# CKT_C70005-A2.net
KiCad netlist of a schematic drawn in Altium Designer
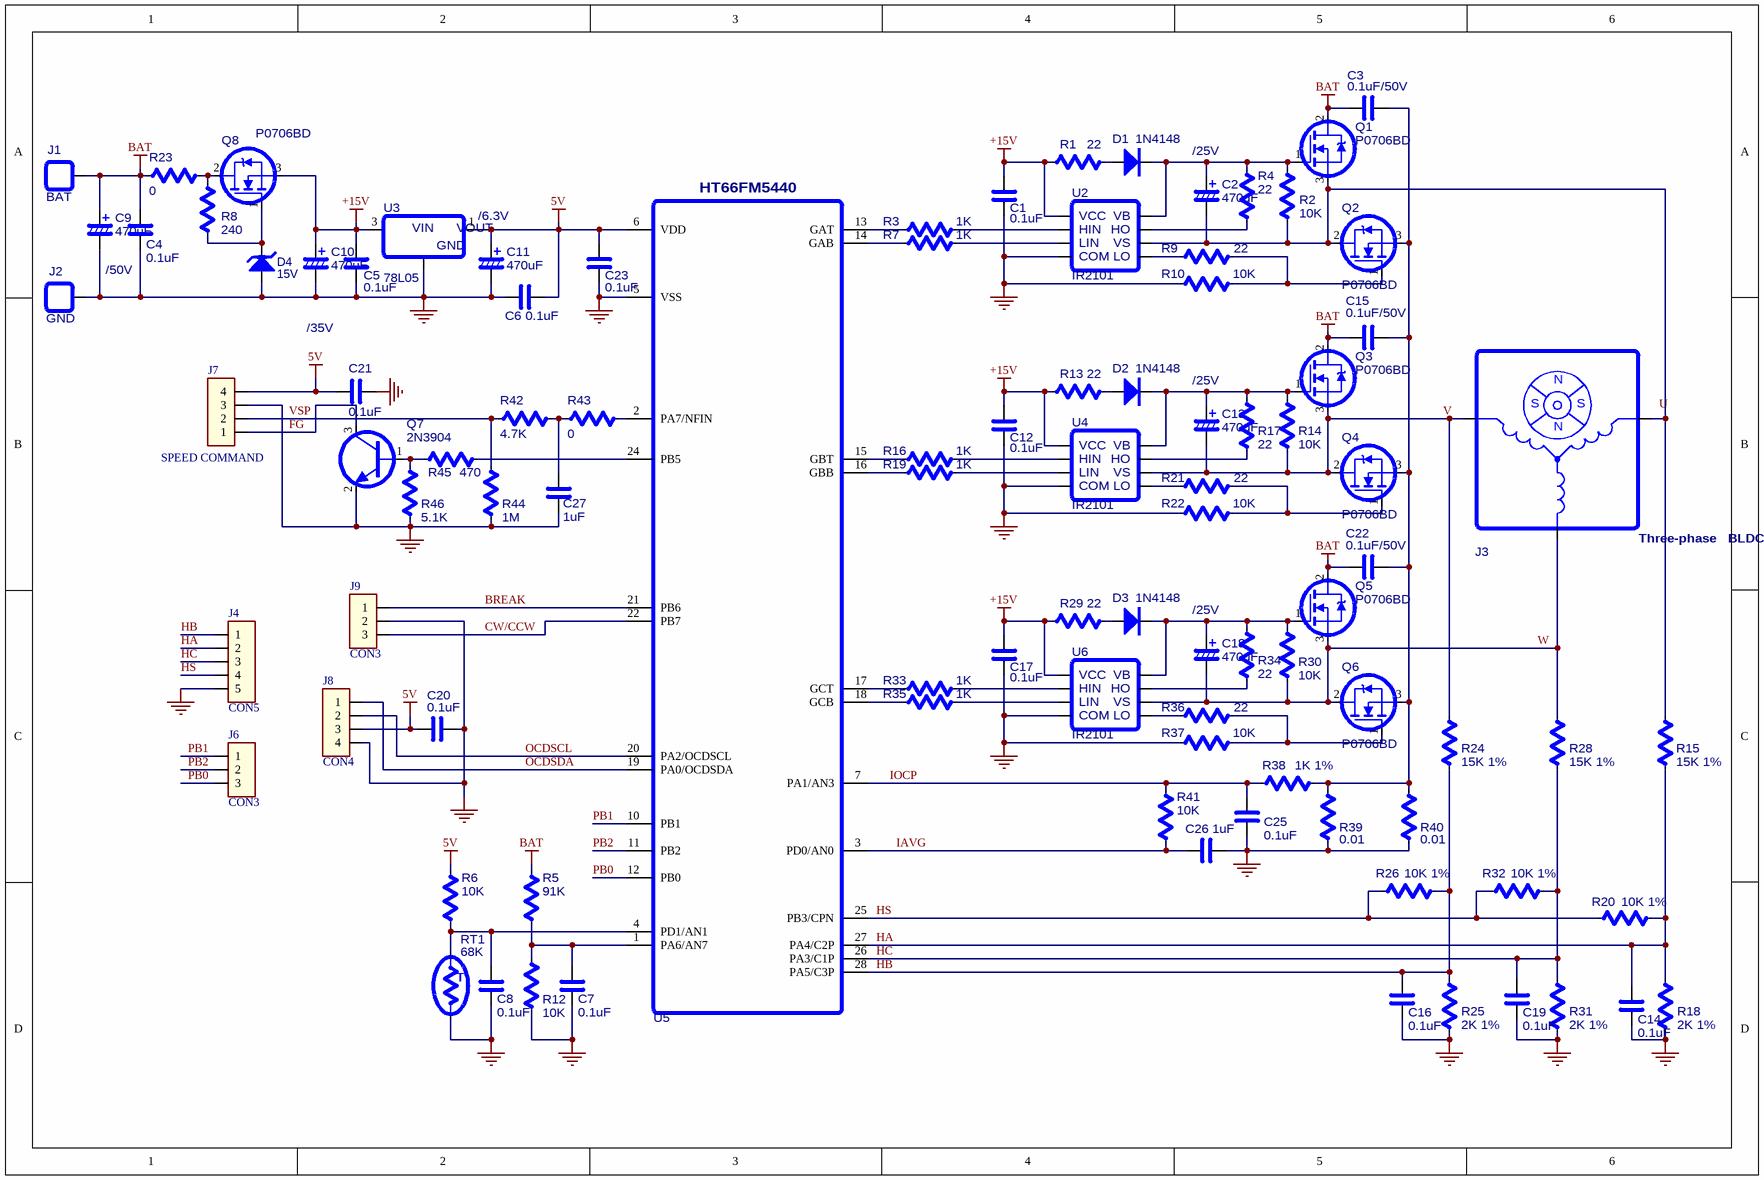
[diagram p0: CKT_C70005-A2.SchDoc]

(export (version "E")
  (design (tool "Eeschema 10.0.6"))
  (components
    (comp (ref "C1")
      (value "0.1uF")
      (description "Capacitor")
      (fields (field (name "PUBLISHER") "Altium Limited"))
      (libsource (lib "Holtek Component Library V2") (part "Cap(1)"))
    )
    (comp (ref "C2")
      (value "470uF")
      (footprint "0805C")
      (description "Capacitor")
      (libsource (lib "C70005") (part "Cap(2)"))
    )
    (comp (ref "C3")
      (value "0.1uF/50V")
      (description "Capacitor")
      (fields (field (name "PUBLISHER") "Altium Limited"))
      (libsource (lib "Holtek Component Library V2") (part "Cap(1)"))
    )
    (comp (ref "C4")
      (value "0.1uF")
      (description "Capacitor")
      (fields (field (name "PUBLISHER") "Altium Limited"))
      (libsource (lib "Holtek Component Library V2") (part "Cap(1)"))
    )
    (comp (ref "C5")
      (value "0.1uF")
      (description "Capacitor")
      (fields (field (name "PUBLISHER") "Altium Limited"))
      (libsource (lib "Holtek Component Library V2") (part "Cap(1)"))
    )
    (comp (ref "C6")
      (value "0.1uF")
      (description "Capacitor")
      (fields (field (name "PUBLISHER") "Altium Limited"))
      (libsource (lib "Holtek Component Library V2") (part "Cap(1)"))
    )
    (comp (ref "C7")
      (value "0.1uF")
      (description "Capacitor")
      (fields (field (name "PUBLISHER") "Altium Limited"))
      (libsource (lib "Holtek Component Library V2") (part "Cap(1)"))
    )
    (comp (ref "C8")
      (value "0.1uF")
      (description "Capacitor")
      (fields (field (name "PUBLISHER") "Altium Limited"))
      (libsource (lib "Holtek Component Library V2") (part "Cap(1)"))
    )
    (comp (ref "C9")
      (value "470uF")
      (footprint "CD-10.5*21")
      (description "Capacitor")
      (libsource (lib "C70005") (part "Cap(2)"))
    )
    (comp (ref "C10")
      (value "470uF")
      (footprint "ECAP 35V47UF")
      (description "Capacitor")
      (libsource (lib "C70005") (part "Cap(2)"))
    )
    (comp (ref "C11")
      (value "470uF")
      (footprint "ECAP 35V47UF")
      (description "Capacitor")
      (libsource (lib "C70005") (part "Cap(2)"))
    )
    (comp (ref "C12")
      (value "0.1uF")
      (description "Capacitor")
      (fields (field (name "PUBLISHER") "Altium Limited"))
      (libsource (lib "Holtek Component Library V2") (part "Cap(1)"))
    )
    (comp (ref "C13")
      (value "470uF")
      (footprint "0805C")
      (description "Capacitor")
      (libsource (lib "C70005") (part "Cap(2)"))
    )
    (comp (ref "C14")
      (value "0.1uF")
      (footprint "0603C")
      (description "Capacitor")
      (fields (field (name "PUBLISHER") "Altium Limited"))
      (libsource (lib "Holtek Component Library V2") (part "Cap(1)"))
    )
    (comp (ref "C15")
      (value "0.1uF/50V")
      (description "Capacitor")
      (fields (field (name "PUBLISHER") "Altium Limited"))
      (libsource (lib "Holtek Component Library V2") (part "Cap(1)"))
    )
    (comp (ref "C16")
      (value "0.1uF")
      (footprint "0603C")
      (description "Capacitor")
      (fields (field (name "PUBLISHER") "Altium Limited"))
      (libsource (lib "Holtek Component Library V2") (part "Cap(1)"))
    )
    (comp (ref "C17")
      (value "0.1uF")
      (description "Capacitor")
      (fields (field (name "PUBLISHER") "Altium Limited"))
      (libsource (lib "Holtek Component Library V2") (part "Cap(1)"))
    )
    (comp (ref "C18")
      (value "470uF")
      (footprint "0805C")
      (description "Capacitor")
      (libsource (lib "C70005") (part "Cap(2)"))
    )
    (comp (ref "C19")
      (value "0.1uF")
      (footprint "0603C")
      (description "Capacitor")
      (fields (field (name "PUBLISHER") "Altium Limited"))
      (libsource (lib "Holtek Component Library V2") (part "Cap(1)"))
    )
    (comp (ref "C20")
      (value "0.1uF")
      (footprint "0603c")
      (description "Capacitor")
      (fields (field (name "PUBLISHER") "Altium Limited"))
      (libsource (lib "Holtek Component Library V2") (part "Cap(1)"))
    )
    (comp (ref "C21")
      (value "0.1uF")
      (footprint "0603c")
      (description "Capacitor")
      (fields (field (name "PUBLISHER") "Altium Limited"))
      (libsource (lib "Holtek Component Library V2") (part "Cap(1)"))
    )
    (comp (ref "C22")
      (value "0.1uF/50V")
      (description "Capacitor")
      (fields (field (name "PUBLISHER") "Altium Limited"))
      (libsource (lib "Holtek Component Library V2") (part "Cap(1)"))
    )
    (comp (ref "C23")
      (value "0.1uF")
      (description "Capacitor")
      (fields (field (name "PUBLISHER") "Altium Limited"))
      (libsource (lib "Holtek Component Library V2") (part "Cap(1)"))
    )
    (comp (ref "C25")
      (value "0.1uF")
      (description "Capacitor")
      (fields (field (name "PUBLISHER") "Altium Limited"))
      (libsource (lib "Holtek Component Library V2") (part "Cap(1)"))
    )
    (comp (ref "C26")
      (value "1uF")
      (description "Capacitor")
      (fields (field (name "PUBLISHER") "Altium Limited"))
      (libsource (lib "Holtek Component Library V2") (part "Cap(1)"))
    )
    (comp (ref "C27")
      (value "1uF")
      (description "Capacitor")
      (fields (field (name "PUBLISHER") "Altium Limited"))
      (libsource (lib "Holtek Component Library V2") (part "Cap(1)"))
    )
    (comp (ref "D1")
      (value "1N4148")
      (footprint "1206D")
      (description "Diode")
      (fields (field (name "PUBLISHER") "Altium Limited"))
      (libsource (lib "Holtek Component Library V2") (part "Diode(1)"))
    )
    (comp (ref "D2")
      (value "1N4148")
      (footprint "1206D")
      (description "Diode")
      (fields (field (name "PUBLISHER") "Altium Limited"))
      (libsource (lib "Holtek Component Library V2") (part "Diode(1)"))
    )
    (comp (ref "D3")
      (value "1N4148")
      (footprint "1206D")
      (description "Diode")
      (fields (field (name "PUBLISHER") "Altium Limited"))
      (libsource (lib "Holtek Component Library V2") (part "Diode(1)"))
    )
    (comp (ref "D4")
      (value "15V")
      (footprint "1206D")
      (description "Zener Diode")
      (libsource (lib "Holtek Component Library V2(Chris)") (part "Zener(1)"))
    )
    (comp (ref "J1")
      (value "BAT")
      (footprint "SIP1-big")
      (description "CON1")
      (fields (field (name "PUBLISHER") "Altium Limited"))
      (libsource (lib "C70005-A1") (part "CON1"))
    )
    (comp (ref "J2")
      (value "GND")
      (footprint "SIP1-big")
      (description "CON1")
      (fields (field (name "PUBLISHER") "Altium Limited"))
      (libsource (lib "C70005-A1") (part "CON1"))
    )
    (comp (ref "J3") (value "BLDC motor(1)") (libsource (lib "C70005") (part "BLDC motor(1)_1")))
    (comp (ref "J4") (value "CON5") (libsource (lib "MYLIB") (part "CON5")))
    (comp (ref "J6") (value "CON3") (libsource (lib "MYLIB") (part "CON3")))
    (comp (ref "J7") (value "SPEED COMMAND") (footprint "HDR1X4") (libsource (lib "") (part "CON4_1")))
    (comp (ref "J8") (value "CON4") (footprint "SIP4") (libsource (lib "MYLIB") (part "CON4")))
    (comp (ref "J9") (value "CON3") (footprint "SIP3-2.54mm") (libsource (lib "") (part "CON3_1")))
    (comp (ref "Q1")
      (value "P0706BD")
      (footprint "TO252")
      (description "N-Channel Power MOSFET")
      (fields (field (name "PUBLISHER") "Altium Limited"))
      (libsource (lib "C70005") (part "NMOS(4)"))
    )
    (comp (ref "Q2")
      (value "P0706BD")
      (footprint "TO252")
      (description "N-Channel Power MOSFET")
      (fields (field (name "PUBLISHER") "Altium Limited"))
      (libsource (lib "C70005") (part "NMOS(4)"))
    )
    (comp (ref "Q3")
      (value "P0706BD")
      (footprint "TO252")
      (description "N-Channel Power MOSFET")
      (fields (field (name "PUBLISHER") "Altium Limited"))
      (libsource (lib "C70005") (part "NMOS(4)"))
    )
    (comp (ref "Q4")
      (value "P0706BD")
      (footprint "TO252")
      (description "N-Channel Power MOSFET")
      (fields (field (name "PUBLISHER") "Altium Limited"))
      (libsource (lib "C70005") (part "NMOS(4)"))
    )
    (comp (ref "Q5")
      (value "P0706BD")
      (footprint "TO252")
      (description "N-Channel Power MOSFET")
      (fields (field (name "PUBLISHER") "Altium Limited"))
      (libsource (lib "C70005") (part "NMOS(4)"))
    )
    (comp (ref "Q6")
      (value "P0706BD")
      (footprint "TO252")
      (description "N-Channel Power MOSFET")
      (fields (field (name "PUBLISHER") "Altium Limited"))
      (libsource (lib "C70005") (part "NMOS(4)"))
    )
    (comp (ref "Q7")
      (value "2N3904")
      (footprint "SOT-23")
      (description "NPN Bipolar Transistor")
      (fields (field (name "PUBLISHER") "Altium Limited"))
      (libsource (lib "C70005") (part "NPN(2)"))
    )
    (comp (ref "Q8")
      (value "P0706BD")
      (footprint "TO252")
      (description "N-Channel Power MOSFET")
      (fields (field (name "PUBLISHER") "Altium Limited"))
      (libsource (lib "C70005") (part "NMOS(4)"))
    )
    (comp (ref "R1")
      (value "22")
      (description "Resisitor")
      (libsource (lib "Holtek Component Library V2") (part "Resistor(1)_1"))
    )
    (comp (ref "R2")
      (value "10K")
      (description "Resisitor")
      (libsource (lib "Holtek Component Library V2") (part "Resistor(1)_1"))
    )
    (comp (ref "R3")
      (value "1K")
      (description "Resisitor")
      (libsource (lib "Holtek Component Library V2") (part "Resistor(1)_1"))
    )
    (comp (ref "R4")
      (value "22")
      (description "Resisitor")
      (libsource (lib "Holtek Component Library V2") (part "Resistor(1)_1"))
    )
    (comp (ref "R5")
      (value "91K")
      (description "Resisitor")
      (libsource (lib "Holtek Component Library V2") (part "Resistor(1)_1"))
    )
    (comp (ref "R6")
      (value "10K")
      (description "Resisitor")
      (libsource (lib "Holtek Component Library V2") (part "Resistor(1)_1"))
    )
    (comp (ref "R7")
      (value "1K")
      (description "Resisitor")
      (libsource (lib "Holtek Component Library V2") (part "Resistor(1)_1"))
    )
    (comp (ref "R8")
      (value "240")
      (description "Resisitor")
      (libsource (lib "Holtek Component Library V2") (part "Resistor(1)_1"))
    )
    (comp (ref "R9")
      (value "22")
      (description "Resisitor")
      (libsource (lib "Holtek Component Library V2") (part "Resistor(1)_1"))
    )
    (comp (ref "R10")
      (value "10K")
      (description "Resisitor")
      (libsource (lib "Holtek Component Library V2") (part "Resistor(1)_1"))
    )
    (comp (ref "R12")
      (value "10K")
      (description "Resisitor")
      (libsource (lib "Holtek Component Library V2") (part "Resistor(1)_1"))
    )
    (comp (ref "R13")
      (value "22")
      (description "Resisitor")
      (libsource (lib "Holtek Component Library V2") (part "Resistor(1)_1"))
    )
    (comp (ref "R14")
      (value "10K")
      (description "Resisitor")
      (libsource (lib "Holtek Component Library V2") (part "Resistor(1)_1"))
    )
    (comp (ref "R15")
      (value "15K 1%")
      (description "Resisitor")
      (libsource (lib "Holtek Component Library V2") (part "Resistor(1)_1"))
    )
    (comp (ref "R16")
      (value "1K")
      (description "Resisitor")
      (libsource (lib "Holtek Component Library V2") (part "Resistor(1)_1"))
    )
    (comp (ref "R17")
      (value "22")
      (description "Resisitor")
      (libsource (lib "Holtek Component Library V2") (part "Resistor(1)_1"))
    )
    (comp (ref "R18")
      (value "2K 1%")
      (description "Resisitor")
      (libsource (lib "Holtek Component Library V2") (part "Resistor(1)_1"))
    )
    (comp (ref "R19")
      (value "1K")
      (description "Resisitor")
      (libsource (lib "Holtek Component Library V2") (part "Resistor(1)_1"))
    )
    (comp (ref "R20")
      (value "10K 1%")
      (description "Resisitor")
      (libsource (lib "Holtek Component Library V2") (part "Resistor(1)_1"))
    )
    (comp (ref "R21")
      (value "22")
      (description "Resisitor")
      (libsource (lib "Holtek Component Library V2") (part "Resistor(1)_1"))
    )
    (comp (ref "R22")
      (value "10K")
      (description "Resisitor")
      (libsource (lib "Holtek Component Library V2") (part "Resistor(1)_1"))
    )
    (comp (ref "R23")
      (value "0")
      (description "Resisitor")
      (libsource (lib "Holtek Component Library V2") (part "Resistor(1)_1"))
    )
    (comp (ref "R24")
      (value "15K 1%")
      (description "Resisitor")
      (libsource (lib "Holtek Component Library V2") (part "Resistor(1)_1"))
    )
    (comp (ref "R25")
      (value "2K 1%")
      (description "Resisitor")
      (libsource (lib "Holtek Component Library V2") (part "Resistor(1)_1"))
    )
    (comp (ref "R26")
      (value "10K 1%")
      (description "Resisitor")
      (libsource (lib "Holtek Component Library V2") (part "Resistor(1)_1"))
    )
    (comp (ref "R28")
      (value "15K 1%")
      (description "Resisitor")
      (libsource (lib "Holtek Component Library V2") (part "Resistor(1)_1"))
    )
    (comp (ref "R29")
      (value "22")
      (description "Resisitor")
      (libsource (lib "Holtek Component Library V2") (part "Resistor(1)_1"))
    )
    (comp (ref "R30")
      (value "10K")
      (description "Resisitor")
      (libsource (lib "Holtek Component Library V2") (part "Resistor(1)_1"))
    )
    (comp (ref "R31")
      (value "2K 1%")
      (description "Resisitor")
      (libsource (lib "Holtek Component Library V2") (part "Resistor(1)_1"))
    )
    (comp (ref "R32")
      (value "10K 1%")
      (description "Resisitor")
      (libsource (lib "Holtek Component Library V2") (part "Resistor(1)_1"))
    )
    (comp (ref "R33")
      (value "1K")
      (description "Resisitor")
      (libsource (lib "Holtek Component Library V2") (part "Resistor(1)_1"))
    )
    (comp (ref "R34")
      (value "22")
      (description "Resisitor")
      (libsource (lib "Holtek Component Library V2") (part "Resistor(1)_1"))
    )
    (comp (ref "R35")
      (value "1K")
      (description "Resisitor")
      (libsource (lib "Holtek Component Library V2") (part "Resistor(1)_1"))
    )
    (comp (ref "R36")
      (value "22")
      (description "Resisitor")
      (libsource (lib "Holtek Component Library V2") (part "Resistor(1)_1"))
    )
    (comp (ref "R37")
      (value "10K")
      (description "Resisitor")
      (libsource (lib "Holtek Component Library V2") (part "Resistor(1)_1"))
    )
    (comp (ref "R38")
      (value "1K 1%")
      (description "Resisitor")
      (libsource (lib "Holtek Component Library V2") (part "Resistor(1)_1"))
    )
    (comp (ref "R39")
      (value "0.01")
      (description "Resisitor")
      (libsource (lib "Holtek Component Library V2") (part "Resistor(1)_1"))
    )
    (comp (ref "R40")
      (value "0.01")
      (description "Resisitor")
      (libsource (lib "Holtek Component Library V2") (part "Resistor(1)_1"))
    )
    (comp (ref "R41")
      (value "10K")
      (description "Resisitor")
      (libsource (lib "Holtek Component Library V2") (part "Resistor(1)_1"))
    )
    (comp (ref "R42")
      (value "4.7K")
      (description "Resisitor")
      (libsource (lib "Holtek Component Library V2") (part "Resistor(1)_1"))
    )
    (comp (ref "R43")
      (value "0")
      (description "Resisitor")
      (libsource (lib "Holtek Component Library V2") (part "Resistor(1)_1"))
    )
    (comp (ref "R44")
      (value "1M")
      (description "Resisitor")
      (libsource (lib "Holtek Component Library V2") (part "Resistor(1)_1"))
    )
    (comp (ref "R45")
      (value "470")
      (description "Resisitor")
      (libsource (lib "Holtek Component Library V2") (part "Resistor(1)_1"))
    )
    (comp (ref "R46")
      (value "5.1K")
      (description "Resisitor")
      (libsource (lib "Holtek Component Library V2") (part "Resistor(1)_1"))
    )
    (comp (ref "RT1") (value "68K") (libsource (lib "Holtek Component Library V2") (part "Sensor(1)")))
    (comp (ref "U2") (value "IR2101") (footprint "SOP-8") (libsource (lib "C70005") (part "IR2101/SOP-8")))
    (comp (ref "U3") (value "78L05") (footprint "SOT-89") (libsource (lib "C70005") (part "78L05_1")))
    (comp (ref "U4") (value "IR2101") (footprint "SOP-8") (libsource (lib "C70005") (part "IR2101/SOP-8")))
    (comp (ref "U5")
      (value "HT66FM5440/28SSOP")
      (footprint "SSOP28")
      (libsource (lib "C70005") (part "HT66FM5440/28SSOP"))
    )
    (comp (ref "U6") (value "IR2101") (footprint "SOP-8") (libsource (lib "C70005") (part "IR2101/SOP-8")))
  )
  (nets
    (net (code "1") (name "+15V") (class "Default")
      (node (ref "C1") (pin "2") (pinfunction "2_2") (pintype "passive"))
      (node (ref "C10") (pin "1") (pinfunction "1_1") (pintype "passive"))
      (node (ref "C12") (pin "2") (pinfunction "2_2") (pintype "passive"))
      (node (ref "C17") (pin "2") (pinfunction "2_2") (pintype "passive"))
      (node (ref "C5") (pin "2") (pinfunction "2_2") (pintype "passive"))
      (node (ref "Q8") (pin "3") (pinfunction "60_3") (pintype "passive"))
      (node (ref "R1") (pin "1") (pinfunction "1_1") (pintype "passive"))
      (node (ref "R13") (pin "1") (pinfunction "1_1") (pintype "passive"))
      (node (ref "R29") (pin "1") (pinfunction "1_1") (pintype "passive"))
      (node (ref "U2") (pin "1") (pinfunction "VCC_1") (pintype "passive"))
      (node (ref "U3") (pin "3") (pinfunction "Vin_3") (pintype "passive"))
      (node (ref "U4") (pin "1") (pinfunction "VCC_1") (pintype "passive"))
      (node (ref "U6") (pin "1") (pinfunction "VCC_1") (pintype "passive"))
    )
    (net (code "2") (name "/BREAK") (class "Default")
      (node (ref "J9") (pin "1") (pinfunction "1_1") (pintype "passive"))
      (node (ref "U5") (pin "21") (pinfunction "PB6_21") (pintype "passive"))
    )
    (net (code "3") (name "/CW{slash}CCW") (class "Default")
      (node (ref "J9") (pin "3") (pinfunction "3_3") (pintype "passive"))
      (node (ref "U5") (pin "22") (pinfunction "PB7_22") (pintype "passive"))
    )
    (net (code "4") (name "/FG") (class "Default")
      (node (ref "J7") (pin "1") (pinfunction "1_1") (pintype "passive"))
      (node (ref "Q7") (pin "3") (pinfunction "C_3") (pintype "passive"))
    )
    (net (code "5") (name "/HA") (class "Default")
      (node (ref "C14") (pin "2") (pinfunction "2_2") (pintype "passive"))
      (node (ref "J4") (pin "2") (pinfunction "2_2") (pintype "passive"))
      (node (ref "R15") (pin "2") (pinfunction "2_2") (pintype "passive"))
      (node (ref "R18") (pin "1") (pinfunction "1_1") (pintype "passive"))
      (node (ref "R20") (pin "2") (pinfunction "2_2") (pintype "passive"))
      (node (ref "U5") (pin "27") (pinfunction "PA4/C2P_27") (pintype "passive"))
    )
    (net (code "6") (name "/HB") (class "Default")
      (node (ref "C16") (pin "2") (pinfunction "2_2") (pintype "passive"))
      (node (ref "J4") (pin "1") (pinfunction "1_1") (pintype "passive"))
      (node (ref "R24") (pin "2") (pinfunction "2_2") (pintype "passive"))
      (node (ref "R25") (pin "1") (pinfunction "1_1") (pintype "passive"))
      (node (ref "R26") (pin "2") (pinfunction "2_2") (pintype "passive"))
      (node (ref "U5") (pin "28") (pinfunction "PA5/C3P_28") (pintype "passive"))
    )
    (net (code "7") (name "/HC") (class "Default")
      (node (ref "C19") (pin "2") (pinfunction "2_2") (pintype "passive"))
      (node (ref "J4") (pin "3") (pinfunction "3_3") (pintype "passive"))
      (node (ref "R28") (pin "2") (pinfunction "2_2") (pintype "passive"))
      (node (ref "R31") (pin "1") (pinfunction "1_1") (pintype "passive"))
      (node (ref "R32") (pin "2") (pinfunction "2_2") (pintype "passive"))
      (node (ref "U5") (pin "26") (pinfunction "PA3/C1P_26") (pintype "passive"))
    )
    (net (code "8") (name "/HS") (class "Default")
      (node (ref "J4") (pin "4") (pinfunction "4_4") (pintype "passive"))
      (node (ref "R20") (pin "1") (pinfunction "1_1") (pintype "passive"))
      (node (ref "R26") (pin "1") (pinfunction "1_1") (pintype "passive"))
      (node (ref "R32") (pin "1") (pinfunction "1_1") (pintype "passive"))
      (node (ref "U5") (pin "25") (pinfunction "PB3/CPN_25") (pintype "passive"))
    )
    (net (code "9") (name "/IAVG") (class "Default")
      (node (ref "C26") (pin "2") (pinfunction "2_2") (pintype "passive"))
      (node (ref "R41") (pin "1") (pinfunction "1_1") (pintype "passive"))
      (node (ref "U5") (pin "3") (pinfunction "PD0/AN0_3") (pintype "passive"))
    )
    (net (code "10") (name "/IOCP") (class "Default")
      (node (ref "C25") (pin "1") (pinfunction "1_1") (pintype "passive"))
      (node (ref "R38") (pin "2") (pinfunction "2_2") (pintype "passive"))
      (node (ref "R41") (pin "2") (pinfunction "2_2") (pintype "passive"))
      (node (ref "U5") (pin "7") (pinfunction "PA1/AN3_7") (pintype "passive"))
    )
    (net (code "11") (name "/OCDSCL") (class "Default")
      (node (ref "J8") (pin "2") (pinfunction "2_2") (pintype "passive"))
      (node (ref "U5") (pin "20") (pinfunction "PA2/OCDSCL_20") (pintype "passive"))
    )
    (net (code "12") (name "/OCDSDA") (class "Default")
      (node (ref "J8") (pin "1") (pinfunction "1_1") (pintype "passive"))
      (node (ref "U5") (pin "19") (pinfunction "PA0/OCDSDA_19") (pintype "passive"))
    )
    (net (code "13") (name "/PB0") (class "Default")
      (node (ref "J6") (pin "3") (pinfunction "3_3") (pintype "passive"))
      (node (ref "U5") (pin "12") (pinfunction "PB0_12") (pintype "passive"))
    )
    (net (code "14") (name "/PB1") (class "Default")
      (node (ref "J6") (pin "1") (pinfunction "1_1") (pintype "passive"))
      (node (ref "U5") (pin "10") (pinfunction "PB1_10") (pintype "passive"))
    )
    (net (code "15") (name "/PB2") (class "Default")
      (node (ref "J6") (pin "2") (pinfunction "2_2") (pintype "passive"))
      (node (ref "U5") (pin "11") (pinfunction "PB2_11") (pintype "passive"))
    )
    (net (code "17") (name "/V") (class "Default")
      (node (ref "C13") (pin "2") (pinfunction "2_2") (pintype "passive"))
      (node (ref "J3") (pin "2") (pinfunction "2_2") (pintype "passive"))
      (node (ref "Q3") (pin "3") (pinfunction "60_3") (pintype "passive"))
      (node (ref "Q4") (pin "2") (pinfunction "D_2") (pintype "passive"))
      (node (ref "R14") (pin "1") (pinfunction "1_1") (pintype "passive"))
      (node (ref "R24") (pin "1") (pinfunction "1_1") (pintype "passive"))
      (node (ref "U4") (pin "6") (pinfunction "VS_6") (pintype "passive"))
    )
    (net (code "18") (name "/VSP") (class "Default")
      (node (ref "J7") (pin "2") (pinfunction "2_2") (pintype "passive"))
      (node (ref "R42") (pin "1") (pinfunction "1_1") (pintype "passive"))
      (node (ref "R44") (pin "2") (pinfunction "2_2") (pintype "passive"))
    )
    (net (code "19") (name "/W") (class "Default")
      (node (ref "C18") (pin "2") (pinfunction "2_2") (pintype "passive"))
      (node (ref "J3") (pin "3") (pinfunction "3_3") (pintype "passive"))
      (node (ref "Q5") (pin "3") (pinfunction "60_3") (pintype "passive"))
      (node (ref "Q6") (pin "2") (pinfunction "D_2") (pintype "passive"))
      (node (ref "R28") (pin "1") (pinfunction "1_1") (pintype "passive"))
      (node (ref "R30") (pin "1") (pinfunction "1_1") (pintype "passive"))
      (node (ref "U6") (pin "6") (pinfunction "VS_6") (pintype "passive"))
    )
    (net (code "20") (name "5V") (class "Default")
      (node (ref "C11") (pin "1") (pinfunction "1_1") (pintype "passive"))
      (node (ref "C20") (pin "1") (pinfunction "1_1") (pintype "passive"))
      (node (ref "C21") (pin "2") (pinfunction "2_2") (pintype "passive"))
      (node (ref "C23") (pin "1") (pinfunction "1_1") (pintype "passive"))
      (node (ref "C6") (pin "1") (pinfunction "1_1") (pintype "passive"))
      (node (ref "J7") (pin "4") (pinfunction "4_4") (pintype "passive"))
      (node (ref "J8") (pin "3") (pinfunction "3_3") (pintype "passive"))
      (node (ref "R6") (pin "2") (pinfunction "2_2") (pintype "passive"))
      (node (ref "U3") (pin "1") (pinfunction "Vout_1") (pintype "passive"))
      (node (ref "U5") (pin "6") (pinfunction "VDD_6") (pintype "passive"))
    )
    (net (code "21") (name "BAT") (class "Default")
      (node (ref "C15") (pin "2") (pinfunction "2_2") (pintype "passive"))
      (node (ref "C22") (pin "2") (pinfunction "2_2") (pintype "passive"))
      (node (ref "C3") (pin "2") (pinfunction "2_2") (pintype "passive"))
      (node (ref "C4") (pin "2") (pinfunction "2_2") (pintype "passive"))
      (node (ref "C9") (pin "1") (pinfunction "1_1") (pintype "passive"))
      (node (ref "J1") (pin "1") (pinfunction "1_1") (pintype "passive"))
      (node (ref "Q1") (pin "2") (pinfunction "D_2") (pintype "passive"))
      (node (ref "Q3") (pin "2") (pinfunction "D_2") (pintype "passive"))
      (node (ref "Q5") (pin "2") (pinfunction "D_2") (pintype "passive"))
      (node (ref "R23") (pin "1") (pinfunction "1_1") (pintype "passive"))
      (node (ref "R5") (pin "2") (pinfunction "2_2") (pintype "passive"))
    )
    (net (code "22") (name "GND") (class "Default")
      (node (ref "C1") (pin "1") (pinfunction "1_1") (pintype "passive"))
      (node (ref "C10") (pin "2") (pinfunction "2_2") (pintype "passive"))
      (node (ref "C11") (pin "2") (pinfunction "2_2") (pintype "passive"))
      (node (ref "C12") (pin "1") (pinfunction "1_1") (pintype "passive"))
      (node (ref "C14") (pin "1") (pinfunction "1_1") (pintype "passive"))
      (node (ref "C16") (pin "1") (pinfunction "1_1") (pintype "passive"))
      (node (ref "C17") (pin "1") (pinfunction "1_1") (pintype "passive"))
      (node (ref "C19") (pin "1") (pinfunction "1_1") (pintype "passive"))
      (node (ref "C20") (pin "2") (pinfunction "2_2") (pintype "passive"))
      (node (ref "C21") (pin "1") (pinfunction "1_1") (pintype "passive"))
      (node (ref "C23") (pin "2") (pinfunction "2_2") (pintype "passive"))
      (node (ref "C25") (pin "2") (pinfunction "2_2") (pintype "passive"))
      (node (ref "C26") (pin "1") (pinfunction "1_1") (pintype "passive"))
      (node (ref "C27") (pin "1") (pinfunction "1_1") (pintype "passive"))
      (node (ref "C4") (pin "1") (pinfunction "1_1") (pintype "passive"))
      (node (ref "C5") (pin "1") (pinfunction "1_1") (pintype "passive"))
      (node (ref "C6") (pin "2") (pinfunction "2_2") (pintype "passive"))
      (node (ref "C7") (pin "1") (pinfunction "1_1") (pintype "passive"))
      (node (ref "C8") (pin "1") (pinfunction "1_1") (pintype "passive"))
      (node (ref "C9") (pin "2") (pinfunction "2_2") (pintype "passive"))
      (node (ref "D4") (pin "1") (pinfunction "A_1") (pintype "passive"))
      (node (ref "J2") (pin "1") (pinfunction "1_1") (pintype "passive"))
      (node (ref "J4") (pin "5") (pinfunction "5_5") (pintype "passive"))
      (node (ref "J7") (pin "3") (pinfunction "3_3") (pintype "passive"))
      (node (ref "J8") (pin "4") (pinfunction "4_4") (pintype "passive"))
      (node (ref "J9") (pin "2") (pinfunction "2_2") (pintype "passive"))
      (node (ref "Q7") (pin "2") (pinfunction "E_2") (pintype "passive"))
      (node (ref "R10") (pin "2") (pinfunction "2_2") (pintype "passive"))
      (node (ref "R12") (pin "1") (pinfunction "1_1") (pintype "passive"))
      (node (ref "R18") (pin "2") (pinfunction "2_2") (pintype "passive"))
      (node (ref "R22") (pin "2") (pinfunction "2_2") (pintype "passive"))
      (node (ref "R25") (pin "2") (pinfunction "2_2") (pintype "passive"))
      (node (ref "R31") (pin "2") (pinfunction "2_2") (pintype "passive"))
      (node (ref "R37") (pin "2") (pinfunction "2_2") (pintype "passive"))
      (node (ref "R39") (pin "2") (pinfunction "2_2") (pintype "passive"))
      (node (ref "R40") (pin "2") (pinfunction "2_2") (pintype "passive"))
      (node (ref "R44") (pin "1") (pinfunction "1_1") (pintype "passive"))
      (node (ref "R46") (pin "1") (pinfunction "1_1") (pintype "passive"))
      (node (ref "RT1") (pin "2") (pinfunction "2_2") (pintype "passive"))
      (node (ref "U2") (pin "4") (pinfunction "COM_4") (pintype "passive"))
      (node (ref "U3") (pin "2") (pinfunction "GND_2") (pintype "passive"))
      (node (ref "U4") (pin "4") (pinfunction "COM_4") (pintype "passive"))
      (node (ref "U5") (pin "5") (pinfunction "VSS_5") (pintype "passive"))
      (node (ref "U6") (pin "4") (pinfunction "COM_4") (pintype "passive"))
    )
    (net (code "23") (name "Net-(C27-Pad2)") (class "Default")
      (node (ref "C27") (pin "2") (pinfunction "2_2") (pintype "passive"))
      (node (ref "R42") (pin "2") (pinfunction "2_2") (pintype "passive"))
      (node (ref "R43") (pin "1") (pinfunction "1_1") (pintype "passive"))
    )
    (net (code "24") (name "Net-(D1-A)") (class "Default")
      (node (ref "D1") (pin "1") (pinfunction "A_1") (pintype "passive"))
      (node (ref "R1") (pin "2") (pinfunction "2_2") (pintype "passive"))
    )
    (net (code "25") (name "Net-(D1-K)") (class "Default")
      (node (ref "C2") (pin "1") (pinfunction "1_1") (pintype "passive"))
      (node (ref "D1") (pin "2") (pinfunction "K_2") (pintype "passive"))
      (node (ref "Q1") (pin "1") (pinfunction "G_1") (pintype "passive"))
      (node (ref "R2") (pin "2") (pinfunction "2_2") (pintype "passive"))
      (node (ref "R4") (pin "1") (pinfunction "1_1") (pintype "passive"))
      (node (ref "U2") (pin "8") (pinfunction "VB_8") (pintype "passive"))
    )
    (net (code "26") (name "Net-(D2-A)") (class "Default")
      (node (ref "D2") (pin "1") (pinfunction "A_1") (pintype "passive"))
      (node (ref "R13") (pin "2") (pinfunction "2_2") (pintype "passive"))
    )
    (net (code "27") (name "Net-(D2-K)") (class "Default")
      (node (ref "C13") (pin "1") (pinfunction "1_1") (pintype "passive"))
      (node (ref "D2") (pin "2") (pinfunction "K_2") (pintype "passive"))
      (node (ref "Q3") (pin "1") (pinfunction "G_1") (pintype "passive"))
      (node (ref "R14") (pin "2") (pinfunction "2_2") (pintype "passive"))
      (node (ref "R17") (pin "2") (pinfunction "2_2") (pintype "passive"))
      (node (ref "U4") (pin "8") (pinfunction "VB_8") (pintype "passive"))
    )
    (net (code "28") (name "Net-(D3-A)") (class "Default")
      (node (ref "D3") (pin "1") (pinfunction "A_1") (pintype "passive"))
      (node (ref "R29") (pin "2") (pinfunction "2_2") (pintype "passive"))
    )
    (net (code "29") (name "Net-(D3-K)") (class "Default")
      (node (ref "C18") (pin "1") (pinfunction "1_1") (pintype "passive"))
      (node (ref "D3") (pin "2") (pinfunction "K_2") (pintype "passive"))
      (node (ref "Q5") (pin "1") (pinfunction "G_1") (pintype "passive"))
      (node (ref "R30") (pin "2") (pinfunction "2_2") (pintype "passive"))
      (node (ref "R34") (pin "2") (pinfunction "2_2") (pintype "passive"))
      (node (ref "U6") (pin "8") (pinfunction "VB_8") (pintype "passive"))
    )
    (net (code "30") (name "Net-(D4-K)") (class "Default")
      (node (ref "D4") (pin "2") (pinfunction "K_2") (pintype "passive"))
      (node (ref "Q8") (pin "1") (pinfunction "G_1") (pintype "passive"))
      (node (ref "R8") (pin "1") (pinfunction "1_1") (pintype "passive"))
    )
    (net (code "31") (name "Net-(Q1-60)") (class "Default")
      (node (ref "C2") (pin "2") (pinfunction "2_2") (pintype "passive"))
      (node (ref "J3") (pin "1") (pinfunction "1_1") (pintype "passive"))
      (node (ref "Q1") (pin "3") (pinfunction "60_3") (pintype "passive"))
      (node (ref "Q2") (pin "2") (pinfunction "D_2") (pintype "passive"))
      (node (ref "R15") (pin "1") (pinfunction "1_1") (pintype "passive"))
      (node (ref "R2") (pin "1") (pinfunction "1_1") (pintype "passive"))
      (node (ref "U2") (pin "6") (pinfunction "VS_6") (pintype "passive"))
    )
    (net (code "32") (name "Net-(Q2-60)") (class "Default")
      (node (ref "C15") (pin "1") (pinfunction "1_1") (pintype "passive"))
      (node (ref "C22") (pin "1") (pinfunction "1_1") (pintype "passive"))
      (node (ref "C3") (pin "1") (pinfunction "1_1") (pintype "passive"))
      (node (ref "Q2") (pin "3") (pinfunction "60_3") (pintype "passive"))
      (node (ref "Q4") (pin "3") (pinfunction "60_3") (pintype "passive"))
      (node (ref "Q6") (pin "3") (pinfunction "60_3") (pintype "passive"))
      (node (ref "R38") (pin "1") (pinfunction "1_1") (pintype "passive"))
      (node (ref "R39") (pin "1") (pinfunction "1_1") (pintype "passive"))
      (node (ref "R40") (pin "1") (pinfunction "1_1") (pintype "passive"))
    )
    (net (code "33") (name "Net-(Q2-G)") (class "Default")
      (node (ref "Q2") (pin "1") (pinfunction "G_1") (pintype "passive"))
      (node (ref "R10") (pin "1") (pinfunction "1_1") (pintype "passive"))
      (node (ref "R9") (pin "2") (pinfunction "2_2") (pintype "passive"))
    )
    (net (code "34") (name "Net-(Q4-G)") (class "Default")
      (node (ref "Q4") (pin "1") (pinfunction "G_1") (pintype "passive"))
      (node (ref "R21") (pin "2") (pinfunction "2_2") (pintype "passive"))
      (node (ref "R22") (pin "1") (pinfunction "1_1") (pintype "passive"))
    )
    (net (code "35") (name "Net-(Q6-G)") (class "Default")
      (node (ref "Q6") (pin "1") (pinfunction "G_1") (pintype "passive"))
      (node (ref "R36") (pin "2") (pinfunction "2_2") (pintype "passive"))
      (node (ref "R37") (pin "1") (pinfunction "1_1") (pintype "passive"))
    )
    (net (code "36") (name "Net-(Q7-B)") (class "Default")
      (node (ref "Q7") (pin "1") (pinfunction "B_1") (pintype "passive"))
      (node (ref "R45") (pin "2") (pinfunction "2_2") (pintype "passive"))
      (node (ref "R46") (pin "2") (pinfunction "2_2") (pintype "passive"))
    )
    (net (code "37") (name "Net-(Q8-D)") (class "Default")
      (node (ref "Q8") (pin "2") (pinfunction "D_2") (pintype "passive"))
      (node (ref "R23") (pin "2") (pinfunction "2_2") (pintype "passive"))
      (node (ref "R8") (pin "2") (pinfunction "2_2") (pintype "passive"))
    )
    (net (code "38") (name "Net-(U2-HIN)") (class "Default")
      (node (ref "R3") (pin "2") (pinfunction "2_2") (pintype "passive"))
      (node (ref "U2") (pin "2") (pinfunction "HIN_2") (pintype "passive"))
    )
    (net (code "39") (name "Net-(U2-HO)") (class "Default")
      (node (ref "R4") (pin "2") (pinfunction "2_2") (pintype "passive"))
      (node (ref "U2") (pin "7") (pinfunction "HO_7") (pintype "passive"))
    )
    (net (code "40") (name "Net-(U2-LIN)") (class "Default")
      (node (ref "R7") (pin "2") (pinfunction "2_2") (pintype "passive"))
      (node (ref "U2") (pin "3") (pinfunction "LIN_3") (pintype "passive"))
    )
    (net (code "41") (name "Net-(U2-LO)") (class "Default")
      (node (ref "R9") (pin "1") (pinfunction "1_1") (pintype "passive"))
      (node (ref "U2") (pin "5") (pinfunction "LO_5") (pintype "passive"))
    )
    (net (code "42") (name "Net-(U4-HIN)") (class "Default")
      (node (ref "R16") (pin "2") (pinfunction "2_2") (pintype "passive"))
      (node (ref "U4") (pin "2") (pinfunction "HIN_2") (pintype "passive"))
    )
    (net (code "43") (name "Net-(U4-HO)") (class "Default")
      (node (ref "R17") (pin "1") (pinfunction "1_1") (pintype "passive"))
      (node (ref "U4") (pin "7") (pinfunction "HO_7") (pintype "passive"))
    )
    (net (code "44") (name "Net-(U4-LIN)") (class "Default")
      (node (ref "R19") (pin "2") (pinfunction "2_2") (pintype "passive"))
      (node (ref "U4") (pin "3") (pinfunction "LIN_3") (pintype "passive"))
    )
    (net (code "45") (name "Net-(U4-LO)") (class "Default")
      (node (ref "R21") (pin "1") (pinfunction "1_1") (pintype "passive"))
      (node (ref "U4") (pin "5") (pinfunction "LO_5") (pintype "passive"))
    )
    (net (code "46") (name "Net-(U5-GAB)") (class "Default")
      (node (ref "R7") (pin "1") (pinfunction "1_1") (pintype "passive"))
      (node (ref "U5") (pin "14") (pinfunction "GAB_14") (pintype "passive"))
    )
    (net (code "47") (name "Net-(U5-GAT)") (class "Default")
      (node (ref "R3") (pin "1") (pinfunction "1_1") (pintype "passive"))
      (node (ref "U5") (pin "13") (pinfunction "GAT_13") (pintype "passive"))
    )
    (net (code "48") (name "Net-(U5-GBB)") (class "Default")
      (node (ref "R19") (pin "1") (pinfunction "1_1") (pintype "passive"))
      (node (ref "U5") (pin "16") (pinfunction "GBB_16") (pintype "passive"))
    )
    (net (code "49") (name "Net-(U5-GBT)") (class "Default")
      (node (ref "R16") (pin "1") (pinfunction "1_1") (pintype "passive"))
      (node (ref "U5") (pin "15") (pinfunction "GBT_15") (pintype "passive"))
    )
    (net (code "50") (name "Net-(U5-GCB)") (class "Default")
      (node (ref "R35") (pin "1") (pinfunction "1_1") (pintype "passive"))
      (node (ref "U5") (pin "18") (pinfunction "GCB_18") (pintype "passive"))
    )
    (net (code "51") (name "Net-(U5-GCT)") (class "Default")
      (node (ref "R33") (pin "1") (pinfunction "1_1") (pintype "passive"))
      (node (ref "U5") (pin "17") (pinfunction "GCT_17") (pintype "passive"))
    )
    (net (code "52") (name "Net-(U5-PA6{slash}AN7)") (class "Default")
      (node (ref "C7") (pin "2") (pinfunction "2_2") (pintype "passive"))
      (node (ref "R12") (pin "2") (pinfunction "2_2") (pintype "passive"))
      (node (ref "R5") (pin "1") (pinfunction "1_1") (pintype "passive"))
      (node (ref "U5") (pin "1") (pinfunction "PA6/AN7_1") (pintype "passive"))
    )
    (net (code "53") (name "Net-(U5-PA7{slash}NFIN)") (class "Default")
      (node (ref "R43") (pin "2") (pinfunction "2_2") (pintype "passive"))
      (node (ref "U5") (pin "2") (pinfunction "PA7/NFIN_2") (pintype "passive"))
    )
    (net (code "54") (name "Net-(U5-PB5)") (class "Default")
      (node (ref "R45") (pin "1") (pinfunction "1_1") (pintype "passive"))
      (node (ref "U5") (pin "24") (pinfunction "PB5_24") (pintype "passive"))
    )
    (net (code "55") (name "Net-(U5-PD1{slash}AN1)") (class "Default")
      (node (ref "C8") (pin "2") (pinfunction "2_2") (pintype "passive"))
      (node (ref "R6") (pin "1") (pinfunction "1_1") (pintype "passive"))
      (node (ref "RT1") (pin "1") (pinfunction "1_1") (pintype "passive"))
      (node (ref "U5") (pin "4") (pinfunction "PD1/AN1_4") (pintype "passive"))
    )
    (net (code "56") (name "Net-(U6-HIN)") (class "Default")
      (node (ref "R33") (pin "2") (pinfunction "2_2") (pintype "passive"))
      (node (ref "U6") (pin "2") (pinfunction "HIN_2") (pintype "passive"))
    )
    (net (code "57") (name "Net-(U6-HO)") (class "Default")
      (node (ref "R34") (pin "1") (pinfunction "1_1") (pintype "passive"))
      (node (ref "U6") (pin "7") (pinfunction "HO_7") (pintype "passive"))
    )
    (net (code "58") (name "Net-(U6-LIN)") (class "Default")
      (node (ref "R35") (pin "2") (pinfunction "2_2") (pintype "passive"))
      (node (ref "U6") (pin "3") (pinfunction "LIN_3") (pintype "passive"))
    )
    (net (code "59") (name "Net-(U6-LO)") (class "Default")
      (node (ref "R36") (pin "1") (pinfunction "1_1") (pintype "passive"))
      (node (ref "U6") (pin "5") (pinfunction "LO_5") (pintype "passive"))
    )
  )
)
